# Flatcaster-sch.net
KiCad netlist of a schematic drawn in Altium Designer
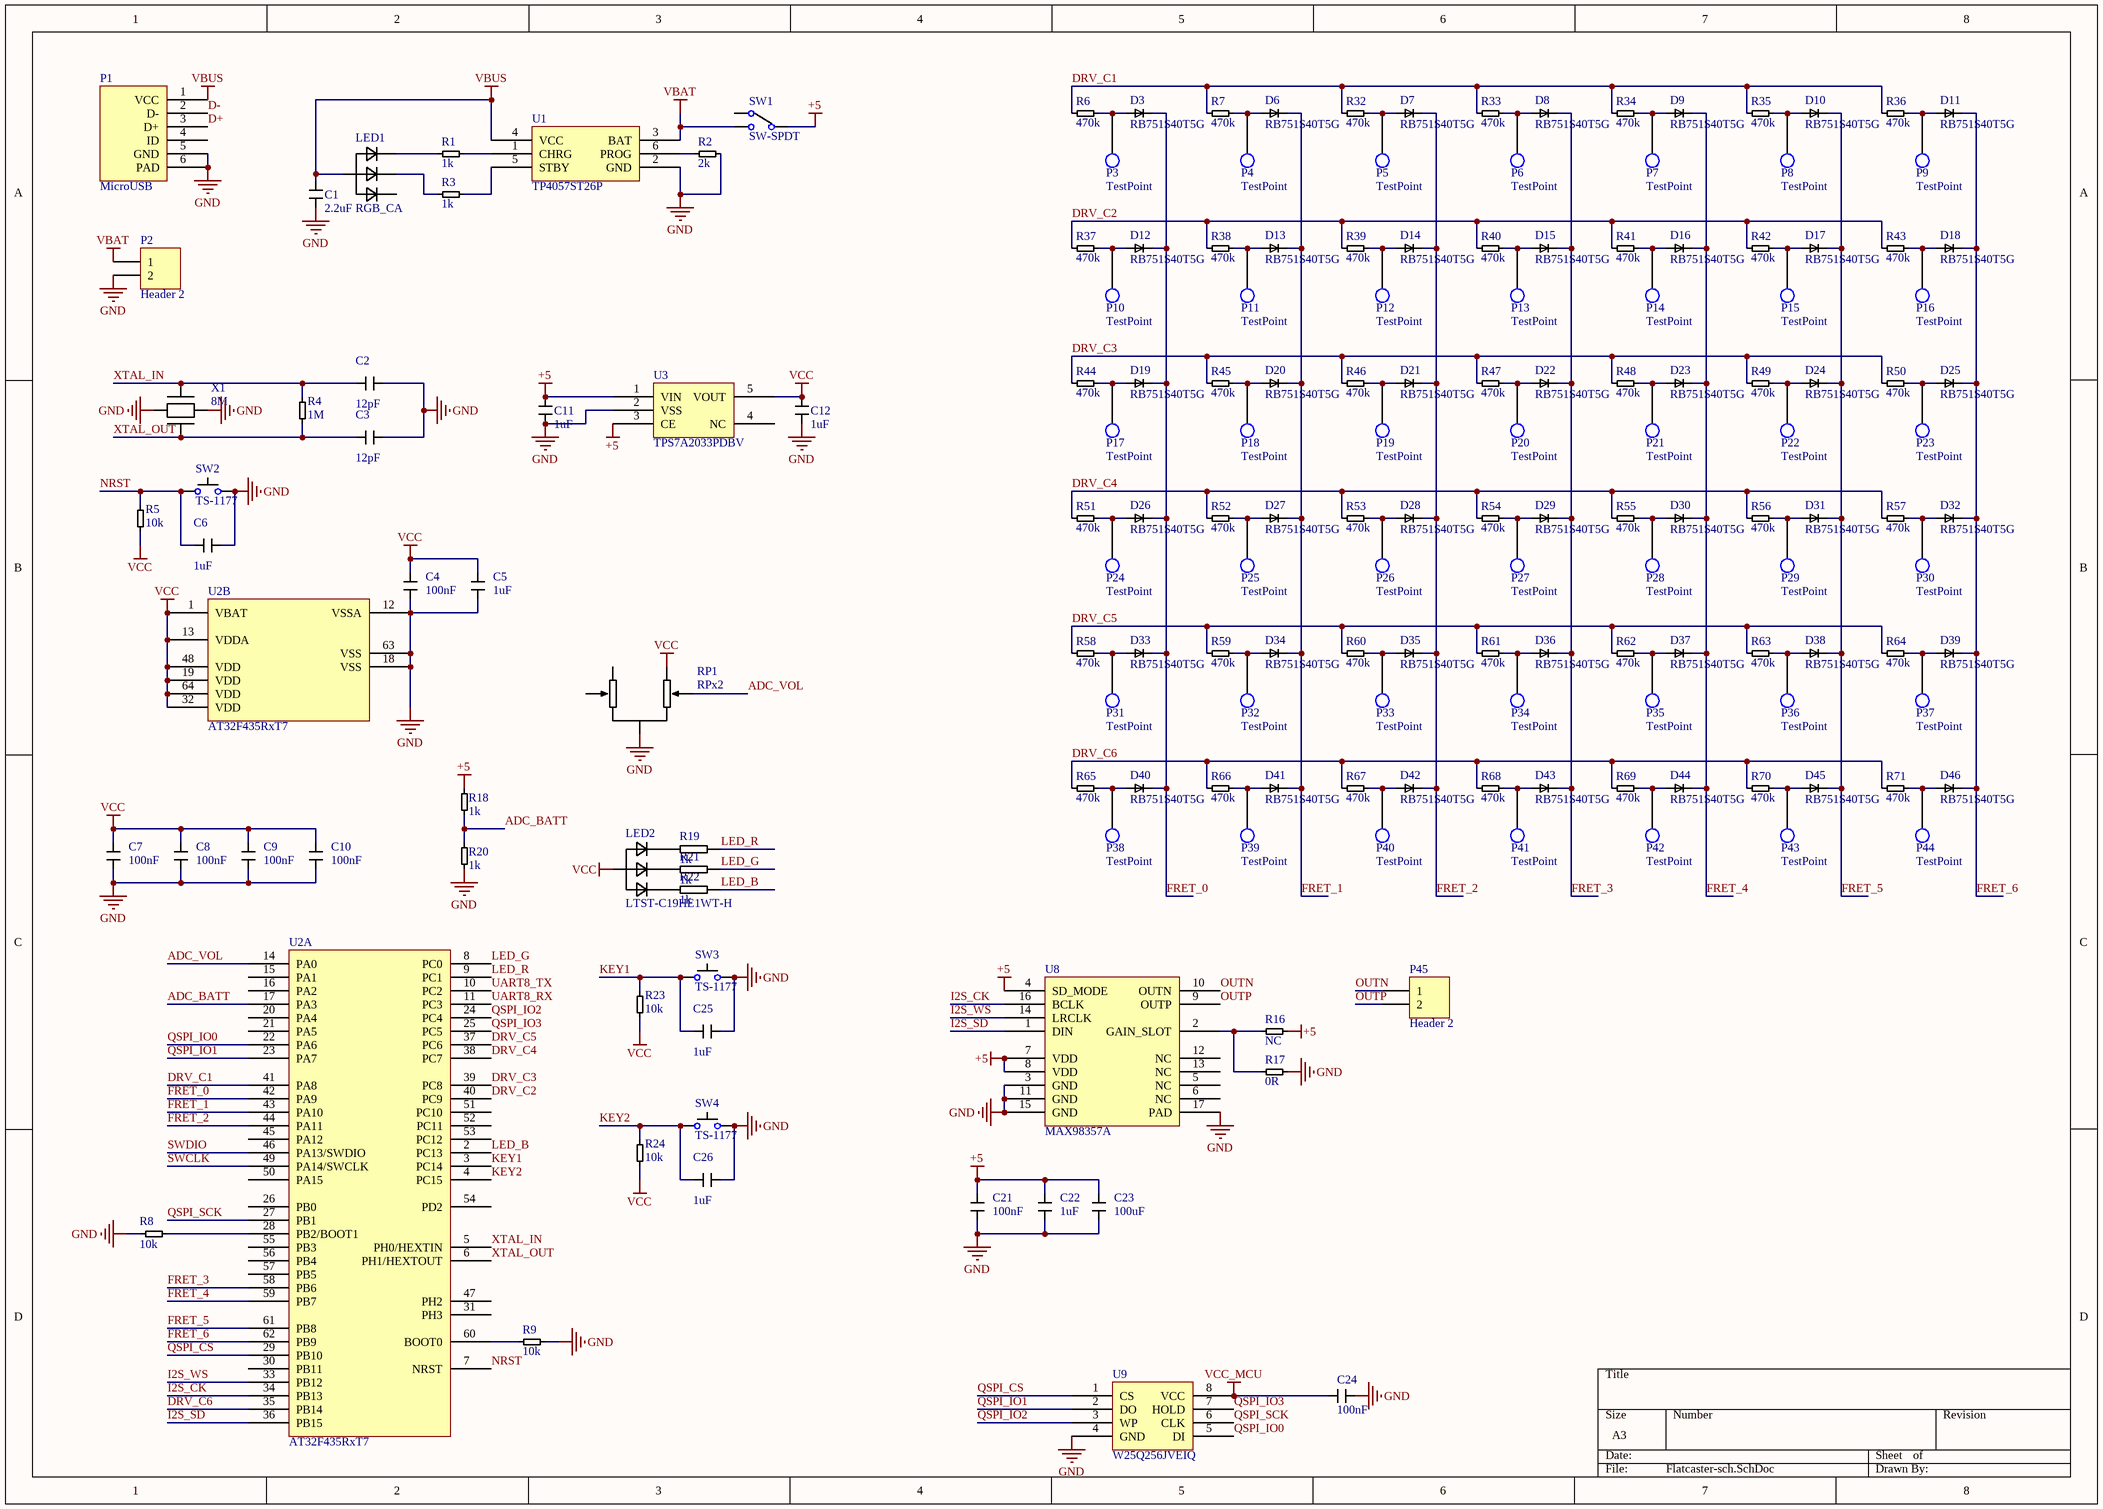
[diagram p0: Flatcaster-sch.SchDoc]

(export (version "E")
  (design (tool "Eeschema 10.0.6"))
  (components
    (comp (ref "C1") (value "2.2uF") (footprint "0603-Cap") (libsource (lib "LibCfrpg") (part "Cap")))
    (comp (ref "C2") (value "12pF") (footprint "0603-Cap") (libsource (lib "LibCfrpg") (part "Cap")))
    (comp (ref "C3") (value "12pF") (footprint "0603-Cap") (libsource (lib "LibCfrpg") (part "Cap")))
    (comp (ref "C4") (value "100nF") (footprint "0603-Cap") (libsource (lib "LibCfrpg") (part "Cap")))
    (comp (ref "C5") (value "1uF") (footprint "0603-Cap") (libsource (lib "LibCfrpg") (part "Cap")))
    (comp (ref "C6") (value "1uF") (footprint "0603-Cap") (libsource (lib "LibCfrpg") (part "Cap")))
    (comp (ref "C7") (value "100nF") (footprint "0603-Cap") (libsource (lib "LibCfrpg") (part "Cap")))
    (comp (ref "C8") (value "100nF") (footprint "0603-Cap") (libsource (lib "LibCfrpg") (part "Cap")))
    (comp (ref "C9") (value "100nF") (footprint "0603-Cap") (libsource (lib "LibCfrpg") (part "Cap")))
    (comp (ref "C10") (value "100nF") (footprint "0603-Cap") (libsource (lib "LibCfrpg") (part "Cap")))
    (comp (ref "C11") (value "1uF") (footprint "0603-Cap") (libsource (lib "LibCfrpg") (part "Cap")))
    (comp (ref "C12") (value "1uF") (footprint "0603-Cap") (libsource (lib "LibCfrpg") (part "Cap")))
    (comp (ref "C21") (value "100nF") (footprint "0603-Cap") (libsource (lib "LibCfrpg") (part "Cap")))
    (comp (ref "C22") (value "1uF") (footprint "0603-Cap") (libsource (lib "LibCfrpg") (part "Cap")))
    (comp (ref "C23") (value "100uF") (footprint "1206-C") (libsource (lib "LibCfrpg") (part "Cap")))
    (comp (ref "C24") (value "100nF") (footprint "0603-Cap") (libsource (lib "LibCfrpg") (part "Cap")))
    (comp (ref "C25") (value "1uF") (footprint "0603-Cap") (libsource (lib "LibCfrpg") (part "Cap")))
    (comp (ref "C26") (value "1uF") (footprint "0603-Cap") (libsource (lib "LibCfrpg") (part "Cap")))
    (comp (ref "D3") (value "RB751S40T5G") (footprint "SOD-523") (libsource (lib "LibCfrpg") (part "Diode")))
    (comp (ref "D6") (value "RB751S40T5G") (footprint "SOD-523") (libsource (lib "LibCfrpg") (part "Diode")))
    (comp (ref "D7") (value "RB751S40T5G") (footprint "SOD-523") (libsource (lib "LibCfrpg") (part "Diode")))
    (comp (ref "D8") (value "RB751S40T5G") (footprint "SOD-523") (libsource (lib "LibCfrpg") (part "Diode")))
    (comp (ref "D9") (value "RB751S40T5G") (footprint "SOD-523") (libsource (lib "LibCfrpg") (part "Diode")))
    (comp (ref "D10") (value "RB751S40T5G") (footprint "SOD-523") (libsource (lib "LibCfrpg") (part "Diode")))
    (comp (ref "D11") (value "RB751S40T5G") (footprint "SOD-523") (libsource (lib "LibCfrpg") (part "Diode")))
    (comp (ref "D12") (value "RB751S40T5G") (footprint "SOD-523") (libsource (lib "LibCfrpg") (part "Diode")))
    (comp (ref "D13") (value "RB751S40T5G") (footprint "SOD-523") (libsource (lib "LibCfrpg") (part "Diode")))
    (comp (ref "D14") (value "RB751S40T5G") (footprint "SOD-523") (libsource (lib "LibCfrpg") (part "Diode")))
    (comp (ref "D15") (value "RB751S40T5G") (footprint "SOD-523") (libsource (lib "LibCfrpg") (part "Diode")))
    (comp (ref "D16") (value "RB751S40T5G") (footprint "SOD-523") (libsource (lib "LibCfrpg") (part "Diode")))
    (comp (ref "D17") (value "RB751S40T5G") (footprint "SOD-523") (libsource (lib "LibCfrpg") (part "Diode")))
    (comp (ref "D18") (value "RB751S40T5G") (footprint "SOD-523") (libsource (lib "LibCfrpg") (part "Diode")))
    (comp (ref "D19") (value "RB751S40T5G") (footprint "SOD-523") (libsource (lib "LibCfrpg") (part "Diode")))
    (comp (ref "D20") (value "RB751S40T5G") (footprint "SOD-523") (libsource (lib "LibCfrpg") (part "Diode")))
    (comp (ref "D21") (value "RB751S40T5G") (footprint "SOD-523") (libsource (lib "LibCfrpg") (part "Diode")))
    (comp (ref "D22") (value "RB751S40T5G") (footprint "SOD-523") (libsource (lib "LibCfrpg") (part "Diode")))
    (comp (ref "D23") (value "RB751S40T5G") (footprint "SOD-523") (libsource (lib "LibCfrpg") (part "Diode")))
    (comp (ref "D24") (value "RB751S40T5G") (footprint "SOD-523") (libsource (lib "LibCfrpg") (part "Diode")))
    (comp (ref "D25") (value "RB751S40T5G") (footprint "SOD-523") (libsource (lib "LibCfrpg") (part "Diode")))
    (comp (ref "D26") (value "RB751S40T5G") (footprint "SOD-523") (libsource (lib "LibCfrpg") (part "Diode")))
    (comp (ref "D27") (value "RB751S40T5G") (footprint "SOD-523") (libsource (lib "LibCfrpg") (part "Diode")))
    (comp (ref "D28") (value "RB751S40T5G") (footprint "SOD-523") (libsource (lib "LibCfrpg") (part "Diode")))
    (comp (ref "D29") (value "RB751S40T5G") (footprint "SOD-523") (libsource (lib "LibCfrpg") (part "Diode")))
    (comp (ref "D30") (value "RB751S40T5G") (footprint "SOD-523") (libsource (lib "LibCfrpg") (part "Diode")))
    (comp (ref "D31") (value "RB751S40T5G") (footprint "SOD-523") (libsource (lib "LibCfrpg") (part "Diode")))
    (comp (ref "D32") (value "RB751S40T5G") (footprint "SOD-523") (libsource (lib "LibCfrpg") (part "Diode")))
    (comp (ref "D33") (value "RB751S40T5G") (footprint "SOD-523") (libsource (lib "LibCfrpg") (part "Diode")))
    (comp (ref "D34") (value "RB751S40T5G") (footprint "SOD-523") (libsource (lib "LibCfrpg") (part "Diode")))
    (comp (ref "D35") (value "RB751S40T5G") (footprint "SOD-523") (libsource (lib "LibCfrpg") (part "Diode")))
    (comp (ref "D36") (value "RB751S40T5G") (footprint "SOD-523") (libsource (lib "LibCfrpg") (part "Diode")))
    (comp (ref "D37") (value "RB751S40T5G") (footprint "SOD-523") (libsource (lib "LibCfrpg") (part "Diode")))
    (comp (ref "D38") (value "RB751S40T5G") (footprint "SOD-523") (libsource (lib "LibCfrpg") (part "Diode")))
    (comp (ref "D39") (value "RB751S40T5G") (footprint "SOD-523") (libsource (lib "LibCfrpg") (part "Diode")))
    (comp (ref "D40") (value "RB751S40T5G") (footprint "SOD-523") (libsource (lib "LibCfrpg") (part "Diode")))
    (comp (ref "D41") (value "RB751S40T5G") (footprint "SOD-523") (libsource (lib "LibCfrpg") (part "Diode")))
    (comp (ref "D42") (value "RB751S40T5G") (footprint "SOD-523") (libsource (lib "LibCfrpg") (part "Diode")))
    (comp (ref "D43") (value "RB751S40T5G") (footprint "SOD-523") (libsource (lib "LibCfrpg") (part "Diode")))
    (comp (ref "D44") (value "RB751S40T5G") (footprint "SOD-523") (libsource (lib "LibCfrpg") (part "Diode")))
    (comp (ref "D45") (value "RB751S40T5G") (footprint "SOD-523") (libsource (lib "LibCfrpg") (part "Diode")))
    (comp (ref "D46") (value "RB751S40T5G") (footprint "SOD-523") (libsource (lib "LibCfrpg") (part "Diode")))
    (comp (ref "LED1") (value "RGB_CA") (footprint "RGB1.6*1.6") (libsource (lib "LibCfrpg") (part "RGB_CA")))
    (comp (ref "LED2")
      (value "LTST-C19HE1WT-H")
      (footprint "RGB1.6*1.6")
      (description "C427425")
      (libsource (lib "LibCfrpg") (part "RGB_CA"))
    )
    (comp (ref "P1") (value "MicroUSB") (footprint "MicroUSB") (libsource (lib "LibCfrpg") (part "MicroUSB")))
    (comp (ref "P2")
      (value "Header 2")
      (footprint "LibCfrpg:SH2.0 2P")
      (description "Header, 2-Pin")
      (fields (field (name "PUBLISHER") "Altium Limited"))
      (libsource (lib "Miscellaneous Connectors") (part "Header 2"))
    )
    (comp (ref "P3")
      (value "TestPoint")
      (footprint "TestPoint")
      (libsource (lib "LibCfrpg") (part "TestPoint"))
    )
    (comp (ref "P4")
      (value "TestPoint")
      (footprint "TestPoint")
      (libsource (lib "LibCfrpg") (part "TestPoint"))
    )
    (comp (ref "P5")
      (value "TestPoint")
      (footprint "TestPoint")
      (libsource (lib "LibCfrpg") (part "TestPoint"))
    )
    (comp (ref "P6")
      (value "TestPoint")
      (footprint "TestPoint")
      (libsource (lib "LibCfrpg") (part "TestPoint"))
    )
    (comp (ref "P7")
      (value "TestPoint")
      (footprint "TestPoint")
      (libsource (lib "LibCfrpg") (part "TestPoint"))
    )
    (comp (ref "P8")
      (value "TestPoint")
      (footprint "TestPoint")
      (libsource (lib "LibCfrpg") (part "TestPoint"))
    )
    (comp (ref "P9")
      (value "TestPoint")
      (footprint "TestPoint")
      (libsource (lib "LibCfrpg") (part "TestPoint"))
    )
    (comp (ref "P10")
      (value "TestPoint")
      (footprint "TestPoint")
      (libsource (lib "LibCfrpg") (part "TestPoint"))
    )
    (comp (ref "P11")
      (value "TestPoint")
      (footprint "TestPoint")
      (libsource (lib "LibCfrpg") (part "TestPoint"))
    )
    (comp (ref "P12")
      (value "TestPoint")
      (footprint "TestPoint")
      (libsource (lib "LibCfrpg") (part "TestPoint"))
    )
    (comp (ref "P13")
      (value "TestPoint")
      (footprint "TestPoint")
      (libsource (lib "LibCfrpg") (part "TestPoint"))
    )
    (comp (ref "P14")
      (value "TestPoint")
      (footprint "TestPoint")
      (libsource (lib "LibCfrpg") (part "TestPoint"))
    )
    (comp (ref "P15")
      (value "TestPoint")
      (footprint "TestPoint")
      (libsource (lib "LibCfrpg") (part "TestPoint"))
    )
    (comp (ref "P16")
      (value "TestPoint")
      (footprint "TestPoint")
      (libsource (lib "LibCfrpg") (part "TestPoint"))
    )
    (comp (ref "P17")
      (value "TestPoint")
      (footprint "TestPoint")
      (libsource (lib "LibCfrpg") (part "TestPoint"))
    )
    (comp (ref "P18")
      (value "TestPoint")
      (footprint "TestPoint")
      (libsource (lib "LibCfrpg") (part "TestPoint"))
    )
    (comp (ref "P19")
      (value "TestPoint")
      (footprint "TestPoint")
      (libsource (lib "LibCfrpg") (part "TestPoint"))
    )
    (comp (ref "P20")
      (value "TestPoint")
      (footprint "TestPoint")
      (libsource (lib "LibCfrpg") (part "TestPoint"))
    )
    (comp (ref "P21")
      (value "TestPoint")
      (footprint "TestPoint")
      (libsource (lib "LibCfrpg") (part "TestPoint"))
    )
    (comp (ref "P22")
      (value "TestPoint")
      (footprint "TestPoint")
      (libsource (lib "LibCfrpg") (part "TestPoint"))
    )
    (comp (ref "P23")
      (value "TestPoint")
      (footprint "TestPoint")
      (libsource (lib "LibCfrpg") (part "TestPoint"))
    )
    (comp (ref "P24")
      (value "TestPoint")
      (footprint "TestPoint")
      (libsource (lib "LibCfrpg") (part "TestPoint"))
    )
    (comp (ref "P25")
      (value "TestPoint")
      (footprint "TestPoint")
      (libsource (lib "LibCfrpg") (part "TestPoint"))
    )
    (comp (ref "P26")
      (value "TestPoint")
      (footprint "TestPoint")
      (libsource (lib "LibCfrpg") (part "TestPoint"))
    )
    (comp (ref "P27")
      (value "TestPoint")
      (footprint "TestPoint")
      (libsource (lib "LibCfrpg") (part "TestPoint"))
    )
    (comp (ref "P28")
      (value "TestPoint")
      (footprint "TestPoint")
      (libsource (lib "LibCfrpg") (part "TestPoint"))
    )
    (comp (ref "P29")
      (value "TestPoint")
      (footprint "TestPoint")
      (libsource (lib "LibCfrpg") (part "TestPoint"))
    )
    (comp (ref "P30")
      (value "TestPoint")
      (footprint "TestPoint")
      (libsource (lib "LibCfrpg") (part "TestPoint"))
    )
    (comp (ref "P31")
      (value "TestPoint")
      (footprint "TestPoint")
      (libsource (lib "LibCfrpg") (part "TestPoint"))
    )
    (comp (ref "P32")
      (value "TestPoint")
      (footprint "TestPoint")
      (libsource (lib "LibCfrpg") (part "TestPoint"))
    )
    (comp (ref "P33")
      (value "TestPoint")
      (footprint "TestPoint")
      (libsource (lib "LibCfrpg") (part "TestPoint"))
    )
    (comp (ref "P34")
      (value "TestPoint")
      (footprint "TestPoint")
      (libsource (lib "LibCfrpg") (part "TestPoint"))
    )
    (comp (ref "P35")
      (value "TestPoint")
      (footprint "TestPoint")
      (libsource (lib "LibCfrpg") (part "TestPoint"))
    )
    (comp (ref "P36")
      (value "TestPoint")
      (footprint "TestPoint")
      (libsource (lib "LibCfrpg") (part "TestPoint"))
    )
    (comp (ref "P37")
      (value "TestPoint")
      (footprint "TestPoint")
      (libsource (lib "LibCfrpg") (part "TestPoint"))
    )
    (comp (ref "P38")
      (value "TestPoint")
      (footprint "TestPoint")
      (libsource (lib "LibCfrpg") (part "TestPoint"))
    )
    (comp (ref "P39")
      (value "TestPoint")
      (footprint "TestPoint")
      (libsource (lib "LibCfrpg") (part "TestPoint"))
    )
    (comp (ref "P40")
      (value "TestPoint")
      (footprint "TestPoint")
      (libsource (lib "LibCfrpg") (part "TestPoint"))
    )
    (comp (ref "P41")
      (value "TestPoint")
      (footprint "TestPoint")
      (libsource (lib "LibCfrpg") (part "TestPoint"))
    )
    (comp (ref "P42")
      (value "TestPoint")
      (footprint "TestPoint")
      (libsource (lib "LibCfrpg") (part "TestPoint"))
    )
    (comp (ref "P43")
      (value "TestPoint")
      (footprint "TestPoint")
      (libsource (lib "LibCfrpg") (part "TestPoint"))
    )
    (comp (ref "P44")
      (value "TestPoint")
      (footprint "TestPoint")
      (libsource (lib "LibCfrpg") (part "TestPoint"))
    )
    (comp (ref "P45")
      (value "Header 2")
      (footprint "HDR1X2")
      (description "Header, 2-Pin")
      (fields (field (name "PUBLISHER") "Altium Limited"))
      (libsource (lib "Miscellaneous Connectors") (part "Header 2"))
    )
    (comp (ref "R1") (value "1k") (footprint "0603") (libsource (lib "LibCfrpg") (part "Res")))
    (comp (ref "R2") (value "2k") (footprint "0603") (libsource (lib "LibCfrpg") (part "Res")))
    (comp (ref "R3") (value "1k") (footprint "0603") (libsource (lib "LibCfrpg") (part "Res")))
    (comp (ref "R4") (value "1M") (footprint "0603") (libsource (lib "LibCfrpg") (part "Res")))
    (comp (ref "R5") (value "10k") (footprint "0603") (libsource (lib "LibCfrpg") (part "Res")))
    (comp (ref "R6") (value "470k") (footprint "0603") (libsource (lib "LibCfrpg") (part "Res")))
    (comp (ref "R7") (value "470k") (footprint "0603") (libsource (lib "LibCfrpg") (part "Res")))
    (comp (ref "R8") (value "10k") (footprint "0603") (libsource (lib "LibCfrpg") (part "Res")))
    (comp (ref "R9") (value "10k") (footprint "0603") (libsource (lib "LibCfrpg") (part "Res")))
    (comp (ref "R16") (value "NC") (footprint "0603") (libsource (lib "LibCfrpg") (part "Res")))
    (comp (ref "R17") (value "0R") (footprint "0603") (libsource (lib "LibCfrpg") (part "Res")))
    (comp (ref "R18") (value "1k") (footprint "0603") (libsource (lib "LibCfrpg") (part "Res")))
    (comp (ref "R19") (value "1k") (footprint "0603") (libsource (lib "") (part "Res_1")))
    (comp (ref "R20") (value "1k") (footprint "0603") (libsource (lib "LibCfrpg") (part "Res")))
    (comp (ref "R21") (value "1k") (footprint "0603") (libsource (lib "") (part "Res_1")))
    (comp (ref "R22") (value "1k") (footprint "0603") (libsource (lib "") (part "Res_1")))
    (comp (ref "R23") (value "10k") (footprint "0603") (libsource (lib "LibCfrpg") (part "Res")))
    (comp (ref "R24") (value "10k") (footprint "0603") (libsource (lib "LibCfrpg") (part "Res")))
    (comp (ref "R32") (value "470k") (footprint "0603") (libsource (lib "LibCfrpg") (part "Res")))
    (comp (ref "R33") (value "470k") (footprint "0603") (libsource (lib "LibCfrpg") (part "Res")))
    (comp (ref "R34") (value "470k") (footprint "0603") (libsource (lib "LibCfrpg") (part "Res")))
    (comp (ref "R35") (value "470k") (footprint "0603") (libsource (lib "LibCfrpg") (part "Res")))
    (comp (ref "R36") (value "470k") (footprint "0603") (libsource (lib "LibCfrpg") (part "Res")))
    (comp (ref "R37") (value "470k") (footprint "0603") (libsource (lib "LibCfrpg") (part "Res")))
    (comp (ref "R38") (value "470k") (footprint "0603") (libsource (lib "LibCfrpg") (part "Res")))
    (comp (ref "R39") (value "470k") (footprint "0603") (libsource (lib "LibCfrpg") (part "Res")))
    (comp (ref "R40") (value "470k") (footprint "0603") (libsource (lib "LibCfrpg") (part "Res")))
    (comp (ref "R41") (value "470k") (footprint "0603") (libsource (lib "LibCfrpg") (part "Res")))
    (comp (ref "R42") (value "470k") (footprint "0603") (libsource (lib "LibCfrpg") (part "Res")))
    (comp (ref "R43") (value "470k") (footprint "0603") (libsource (lib "LibCfrpg") (part "Res")))
    (comp (ref "R44") (value "470k") (footprint "0603") (libsource (lib "LibCfrpg") (part "Res")))
    (comp (ref "R45") (value "470k") (footprint "0603") (libsource (lib "LibCfrpg") (part "Res")))
    (comp (ref "R46") (value "470k") (footprint "0603") (libsource (lib "LibCfrpg") (part "Res")))
    (comp (ref "R47") (value "470k") (footprint "0603") (libsource (lib "LibCfrpg") (part "Res")))
    (comp (ref "R48") (value "470k") (footprint "0603") (libsource (lib "LibCfrpg") (part "Res")))
    (comp (ref "R49") (value "470k") (footprint "0603") (libsource (lib "LibCfrpg") (part "Res")))
    (comp (ref "R50") (value "470k") (footprint "0603") (libsource (lib "LibCfrpg") (part "Res")))
    (comp (ref "R51") (value "470k") (footprint "0603") (libsource (lib "LibCfrpg") (part "Res")))
    (comp (ref "R52") (value "470k") (footprint "0603") (libsource (lib "LibCfrpg") (part "Res")))
    (comp (ref "R53") (value "470k") (footprint "0603") (libsource (lib "LibCfrpg") (part "Res")))
    (comp (ref "R54") (value "470k") (footprint "0603") (libsource (lib "LibCfrpg") (part "Res")))
    (comp (ref "R55") (value "470k") (footprint "0603") (libsource (lib "LibCfrpg") (part "Res")))
    (comp (ref "R56") (value "470k") (footprint "0603") (libsource (lib "LibCfrpg") (part "Res")))
    (comp (ref "R57") (value "470k") (footprint "0603") (libsource (lib "LibCfrpg") (part "Res")))
    (comp (ref "R58") (value "470k") (footprint "0603") (libsource (lib "LibCfrpg") (part "Res")))
    (comp (ref "R59") (value "470k") (footprint "0603") (libsource (lib "LibCfrpg") (part "Res")))
    (comp (ref "R60") (value "470k") (footprint "0603") (libsource (lib "LibCfrpg") (part "Res")))
    (comp (ref "R61") (value "470k") (footprint "0603") (libsource (lib "LibCfrpg") (part "Res")))
    (comp (ref "R62") (value "470k") (footprint "0603") (libsource (lib "LibCfrpg") (part "Res")))
    (comp (ref "R63") (value "470k") (footprint "0603") (libsource (lib "LibCfrpg") (part "Res")))
    (comp (ref "R64") (value "470k") (footprint "0603") (libsource (lib "LibCfrpg") (part "Res")))
    (comp (ref "R65") (value "470k") (footprint "0603") (libsource (lib "LibCfrpg") (part "Res")))
    (comp (ref "R66") (value "470k") (footprint "0603") (libsource (lib "LibCfrpg") (part "Res")))
    (comp (ref "R67") (value "470k") (footprint "0603") (libsource (lib "LibCfrpg") (part "Res")))
    (comp (ref "R68") (value "470k") (footprint "0603") (libsource (lib "LibCfrpg") (part "Res")))
    (comp (ref "R69") (value "470k") (footprint "0603") (libsource (lib "LibCfrpg") (part "Res")))
    (comp (ref "R70") (value "470k") (footprint "0603") (libsource (lib "LibCfrpg") (part "Res")))
    (comp (ref "R71") (value "470k") (footprint "0603") (libsource (lib "LibCfrpg") (part "Res")))
    (comp (ref "RP1") (value "RPx2") (footprint "RK10J") (libsource (lib "LibCfrpg") (part "RPx2")))
    (comp (ref "SW1")
      (value "SW-SPDT")
      (footprint "TA-3524A-A1")
      (description "C514014")
      (libsource (lib "LibCfrpg") (part "SW-SPDT"))
    )
    (comp (ref "SW2")
      (value "TS-1177")
      (footprint "BTN3*3")
      (description "C561512")
      (libsource (lib "LibCfrpg") (part "Btn"))
    )
    (comp (ref "SW3")
      (value "TS-1177")
      (footprint "BTN3*3")
      (description "C561512")
      (libsource (lib "LibCfrpg") (part "Btn"))
    )
    (comp (ref "SW4")
      (value "TS-1177")
      (footprint "BTN3*3")
      (description "C561512")
      (libsource (lib "LibCfrpg") (part "Btn"))
    )
    (comp (ref "U1")
      (value "TP4057ST26P")
      (footprint "SOT236")
      (libsource (lib "LibCfrpg") (part "TP4057ST26P"))
    )
    (comp (ref "U2")
      (value "AT32F435RxT7")
      (footprint "LQFP-64")
      (libsource (lib "LibCfrpg") (part "AT32F435RxT7"))
    )
    (comp (ref "U3")
      (value "TPS7A2033PDBV")
      (footprint "SOT23-5")
      (libsource (lib "LibCfrpg") (part "ME6211"))
    )
    (comp (ref "U8")
      (value "MAX98357A")
      (footprint "QFN16-0.5-1.1PAD")
      (libsource (lib "LibCfrpg") (part "MAX98357A"))
    )
    (comp (ref "U9")
      (value "W25Q256JVEIQ")
      (footprint "WPDFN-8-6x5")
      (libsource (lib "LibCfrpg") (part "W25QxxxVE/A"))
    )
    (comp (ref "X1")
      (value "8M")
      (footprint "XTAL-3225-4P")
      (description "C2682774")
      (libsource (lib "LibCfrpg") (part "XTAL-4LEAD"))
    )
  )
  (nets
    (net (code "1") (name "+5") (class "Default")
      (node (ref "C11") (pin "2") (pintype "passive"))
      (node (ref "C21") (pin "2") (pintype "passive"))
      (node (ref "C22") (pin "2") (pintype "passive"))
      (node (ref "C23") (pin "2") (pintype "passive"))
      (node (ref "R16") (pin "1") (pintype "passive"))
      (node (ref "R18") (pin "2") (pintype "passive"))
      (node (ref "SW1") (pin "1") (pintype "passive"))
      (node (ref "U3") (pin "1") (pinfunction "VIN_1") (pintype "passive"))
      (node (ref "U3") (pin "3") (pinfunction "CE_3") (pintype "passive"))
      (node (ref "U8") (pin "4") (pinfunction "SD_MODE_4") (pintype "passive"))
      (node (ref "U8") (pin "7") (pinfunction "VDD_7") (pintype "passive"))
      (node (ref "U8") (pin "8") (pinfunction "VDD_8") (pintype "passive"))
    )
    (net (code "2") (name "/ADC_BATT") (class "Default")
      (node (ref "R18") (pin "1") (pintype "passive"))
      (node (ref "R20") (pin "2") (pintype "passive"))
      (node (ref "U2") (pin "17") (pinfunction "PA3_17") (pintype "passive"))
    )
    (net (code "3") (name "/ADC_VOL") (class "Default")
      (node (ref "RP1") (pin "3") (pintype "passive"))
      (node (ref "U2") (pin "14") (pinfunction "PA0_14") (pintype "passive"))
    )
    (net (code "4") (name "/D+") (class "Default")
      (node (ref "P1") (pin "3") (pinfunction "D+_3") (pintype "passive"))
    )
    (net (code "5") (name "/D-") (class "Default")
      (node (ref "P1") (pin "2") (pinfunction "D-_2") (pintype "passive"))
    )
    (net (code "6") (name "/DRV_C1") (class "Default")
      (node (ref "R32") (pin "1") (pintype "passive"))
      (node (ref "R33") (pin "1") (pintype "passive"))
      (node (ref "R34") (pin "1") (pintype "passive"))
      (node (ref "R35") (pin "1") (pintype "passive"))
      (node (ref "R36") (pin "1") (pintype "passive"))
      (node (ref "R6") (pin "1") (pintype "passive"))
      (node (ref "R7") (pin "1") (pintype "passive"))
      (node (ref "U2") (pin "41") (pinfunction "PA8_41") (pintype "passive"))
    )
    (net (code "7") (name "/DRV_C2") (class "Default")
      (node (ref "R37") (pin "1") (pintype "passive"))
      (node (ref "R38") (pin "1") (pintype "passive"))
      (node (ref "R39") (pin "1") (pintype "passive"))
      (node (ref "R40") (pin "1") (pintype "passive"))
      (node (ref "R41") (pin "1") (pintype "passive"))
      (node (ref "R42") (pin "1") (pintype "passive"))
      (node (ref "R43") (pin "1") (pintype "passive"))
      (node (ref "U2") (pin "40") (pinfunction "PC9_40") (pintype "passive"))
    )
    (net (code "8") (name "/DRV_C3") (class "Default")
      (node (ref "R44") (pin "1") (pintype "passive"))
      (node (ref "R45") (pin "1") (pintype "passive"))
      (node (ref "R46") (pin "1") (pintype "passive"))
      (node (ref "R47") (pin "1") (pintype "passive"))
      (node (ref "R48") (pin "1") (pintype "passive"))
      (node (ref "R49") (pin "1") (pintype "passive"))
      (node (ref "R50") (pin "1") (pintype "passive"))
      (node (ref "U2") (pin "39") (pinfunction "PC8_39") (pintype "passive"))
    )
    (net (code "9") (name "/DRV_C4") (class "Default")
      (node (ref "R51") (pin "1") (pintype "passive"))
      (node (ref "R52") (pin "1") (pintype "passive"))
      (node (ref "R53") (pin "1") (pintype "passive"))
      (node (ref "R54") (pin "1") (pintype "passive"))
      (node (ref "R55") (pin "1") (pintype "passive"))
      (node (ref "R56") (pin "1") (pintype "passive"))
      (node (ref "R57") (pin "1") (pintype "passive"))
      (node (ref "U2") (pin "38") (pinfunction "PC7_38") (pintype "passive"))
    )
    (net (code "10") (name "/DRV_C5") (class "Default")
      (node (ref "R58") (pin "1") (pintype "passive"))
      (node (ref "R59") (pin "1") (pintype "passive"))
      (node (ref "R60") (pin "1") (pintype "passive"))
      (node (ref "R61") (pin "1") (pintype "passive"))
      (node (ref "R62") (pin "1") (pintype "passive"))
      (node (ref "R63") (pin "1") (pintype "passive"))
      (node (ref "R64") (pin "1") (pintype "passive"))
      (node (ref "U2") (pin "37") (pinfunction "PC6_37") (pintype "passive"))
    )
    (net (code "11") (name "/DRV_C6") (class "Default")
      (node (ref "R65") (pin "1") (pintype "passive"))
      (node (ref "R66") (pin "1") (pintype "passive"))
      (node (ref "R67") (pin "1") (pintype "passive"))
      (node (ref "R68") (pin "1") (pintype "passive"))
      (node (ref "R69") (pin "1") (pintype "passive"))
      (node (ref "R70") (pin "1") (pintype "passive"))
      (node (ref "R71") (pin "1") (pintype "passive"))
      (node (ref "U2") (pin "35") (pinfunction "PB14_35") (pintype "passive"))
    )
    (net (code "12") (name "/FRET_0") (class "Default")
      (node (ref "D12") (pin "2") (pintype "passive"))
      (node (ref "D19") (pin "2") (pintype "passive"))
      (node (ref "D26") (pin "2") (pintype "passive"))
      (node (ref "D3") (pin "2") (pintype "passive"))
      (node (ref "D33") (pin "2") (pintype "passive"))
      (node (ref "D40") (pin "2") (pintype "passive"))
      (node (ref "U2") (pin "42") (pinfunction "PA9_42") (pintype "passive"))
    )
    (net (code "13") (name "/FRET_1") (class "Default")
      (node (ref "D13") (pin "2") (pintype "passive"))
      (node (ref "D20") (pin "2") (pintype "passive"))
      (node (ref "D27") (pin "2") (pintype "passive"))
      (node (ref "D34") (pin "2") (pintype "passive"))
      (node (ref "D41") (pin "2") (pintype "passive"))
      (node (ref "D6") (pin "2") (pintype "passive"))
      (node (ref "U2") (pin "43") (pinfunction "PA10_43") (pintype "passive"))
    )
    (net (code "14") (name "/FRET_2") (class "Default")
      (node (ref "D14") (pin "2") (pintype "passive"))
      (node (ref "D21") (pin "2") (pintype "passive"))
      (node (ref "D28") (pin "2") (pintype "passive"))
      (node (ref "D35") (pin "2") (pintype "passive"))
      (node (ref "D42") (pin "2") (pintype "passive"))
      (node (ref "D7") (pin "2") (pintype "passive"))
      (node (ref "U2") (pin "44") (pinfunction "PA11_44") (pintype "passive"))
    )
    (net (code "15") (name "/FRET_3") (class "Default")
      (node (ref "D15") (pin "2") (pintype "passive"))
      (node (ref "D22") (pin "2") (pintype "passive"))
      (node (ref "D29") (pin "2") (pintype "passive"))
      (node (ref "D36") (pin "2") (pintype "passive"))
      (node (ref "D43") (pin "2") (pintype "passive"))
      (node (ref "D8") (pin "2") (pintype "passive"))
      (node (ref "U2") (pin "58") (pinfunction "PB6_58") (pintype "passive"))
    )
    (net (code "16") (name "/FRET_4") (class "Default")
      (node (ref "D16") (pin "2") (pintype "passive"))
      (node (ref "D23") (pin "2") (pintype "passive"))
      (node (ref "D30") (pin "2") (pintype "passive"))
      (node (ref "D37") (pin "2") (pintype "passive"))
      (node (ref "D44") (pin "2") (pintype "passive"))
      (node (ref "D9") (pin "2") (pintype "passive"))
      (node (ref "U2") (pin "59") (pinfunction "PB7_59") (pintype "passive"))
    )
    (net (code "17") (name "/FRET_5") (class "Default")
      (node (ref "D10") (pin "2") (pintype "passive"))
      (node (ref "D17") (pin "2") (pintype "passive"))
      (node (ref "D24") (pin "2") (pintype "passive"))
      (node (ref "D31") (pin "2") (pintype "passive"))
      (node (ref "D38") (pin "2") (pintype "passive"))
      (node (ref "D45") (pin "2") (pintype "passive"))
      (node (ref "U2") (pin "61") (pinfunction "PB8_61") (pintype "passive"))
    )
    (net (code "18") (name "/FRET_6") (class "Default")
      (node (ref "D11") (pin "2") (pintype "passive"))
      (node (ref "D18") (pin "2") (pintype "passive"))
      (node (ref "D25") (pin "2") (pintype "passive"))
      (node (ref "D32") (pin "2") (pintype "passive"))
      (node (ref "D39") (pin "2") (pintype "passive"))
      (node (ref "D46") (pin "2") (pintype "passive"))
      (node (ref "U2") (pin "62") (pinfunction "PB9_62") (pintype "passive"))
    )
    (net (code "19") (name "/I2S_CK") (class "Default")
      (node (ref "U2") (pin "34") (pinfunction "PB13_34") (pintype "passive"))
      (node (ref "U8") (pin "16") (pinfunction "BCLK_16") (pintype "passive"))
    )
    (net (code "20") (name "/I2S_SD") (class "Default")
      (node (ref "U2") (pin "36") (pinfunction "PB15_36") (pintype "passive"))
      (node (ref "U8") (pin "1") (pinfunction "DIN_1") (pintype "passive"))
    )
    (net (code "21") (name "/I2S_WS") (class "Default")
      (node (ref "U2") (pin "33") (pinfunction "PB12_33") (pintype "passive"))
      (node (ref "U8") (pin "14") (pinfunction "LRCLK_14") (pintype "passive"))
    )
    (net (code "22") (name "/KEY1") (class "Default")
      (node (ref "C25") (pin "2") (pintype "passive"))
      (node (ref "R23") (pin "2") (pintype "passive"))
      (node (ref "SW3") (pin "1") (pintype "passive"))
      (node (ref "U2") (pin "3") (pinfunction "PC14_3") (pintype "passive"))
    )
    (net (code "23") (name "/KEY2") (class "Default")
      (node (ref "C26") (pin "2") (pintype "passive"))
      (node (ref "R24") (pin "2") (pintype "passive"))
      (node (ref "SW4") (pin "1") (pintype "passive"))
      (node (ref "U2") (pin "4") (pinfunction "PC15_4") (pintype "passive"))
    )
    (net (code "24") (name "/LED_B") (class "Default")
      (node (ref "R22") (pin "2") (pintype "passive"))
      (node (ref "U2") (pin "2") (pinfunction "PC13_2") (pintype "passive"))
    )
    (net (code "25") (name "/LED_G") (class "Default")
      (node (ref "R21") (pin "2") (pintype "passive"))
      (node (ref "U2") (pin "8") (pinfunction "PC0_8") (pintype "passive"))
    )
    (net (code "26") (name "/LED_R") (class "Default")
      (node (ref "R19") (pin "2") (pintype "passive"))
      (node (ref "U2") (pin "9") (pinfunction "PC1_9") (pintype "passive"))
    )
    (net (code "27") (name "/NRST") (class "Default")
      (node (ref "C6") (pin "2") (pintype "passive"))
      (node (ref "R5") (pin "2") (pintype "passive"))
      (node (ref "SW2") (pin "1") (pintype "passive"))
      (node (ref "U2") (pin "7") (pinfunction "NRST_7") (pintype "passive"))
    )
    (net (code "28") (name "/OUTN") (class "Default")
      (node (ref "P45") (pin "1") (pinfunction "1_1") (pintype "passive"))
      (node (ref "U8") (pin "10") (pinfunction "OUTN_10") (pintype "passive"))
    )
    (net (code "29") (name "/OUTP") (class "Default")
      (node (ref "P45") (pin "2") (pinfunction "2_2") (pintype "passive"))
      (node (ref "U8") (pin "9") (pinfunction "OUTP_9") (pintype "passive"))
    )
    (net (code "30") (name "/QSPI_CS") (class "Default")
      (node (ref "U2") (pin "29") (pinfunction "PB10_29") (pintype "passive"))
      (node (ref "U9") (pin "1") (pinfunction "CS_1") (pintype "passive"))
    )
    (net (code "31") (name "/QSPI_IO0") (class "Default")
      (node (ref "U2") (pin "22") (pinfunction "PA6_22") (pintype "passive"))
      (node (ref "U9") (pin "5") (pinfunction "DI_5") (pintype "passive"))
    )
    (net (code "32") (name "/QSPI_IO1") (class "Default")
      (node (ref "U2") (pin "23") (pinfunction "PA7_23") (pintype "passive"))
      (node (ref "U9") (pin "2") (pinfunction "DO_2") (pintype "passive"))
    )
    (net (code "33") (name "/QSPI_IO2") (class "Default")
      (node (ref "U2") (pin "24") (pinfunction "PC4_24") (pintype "passive"))
      (node (ref "U9") (pin "3") (pinfunction "WP_3") (pintype "passive"))
    )
    (net (code "34") (name "/QSPI_IO3") (class "Default")
      (node (ref "U2") (pin "25") (pinfunction "PC5_25") (pintype "passive"))
      (node (ref "U9") (pin "7") (pinfunction "HOLD_7") (pintype "passive"))
    )
    (net (code "35") (name "/QSPI_SCK") (class "Default")
      (node (ref "U2") (pin "27") (pinfunction "PB1_27") (pintype "passive"))
      (node (ref "U9") (pin "6") (pinfunction "CLK_6") (pintype "passive"))
    )
    (net (code "36") (name "/SWCLK") (class "Default")
      (node (ref "U2") (pin "49") (pinfunction "PA14/SWCLK_49") (pintype "passive"))
    )
    (net (code "37") (name "/SWDIO") (class "Default")
      (node (ref "U2") (pin "46") (pinfunction "PA13/SWDIO_46") (pintype "passive"))
    )
    (net (code "38") (name "/UART8_RX") (class "Default")
      (node (ref "U2") (pin "11") (pinfunction "PC3_11") (pintype "passive"))
    )
    (net (code "39") (name "/UART8_TX") (class "Default")
      (node (ref "U2") (pin "10") (pinfunction "PC2_10") (pintype "passive"))
    )
    (net (code "40") (name "/XTAL_IN") (class "Default")
      (node (ref "C2") (pin "2") (pintype "passive"))
      (node (ref "R4") (pin "2") (pintype "passive"))
      (node (ref "U2") (pin "5") (pinfunction "PH0/HEXTIN_5") (pintype "passive"))
      (node (ref "X1") (pin "3") (pintype "passive"))
    )
    (net (code "41") (name "/XTAL_OUT") (class "Default")
      (node (ref "C3") (pin "2") (pintype "passive"))
      (node (ref "R4") (pin "1") (pintype "passive"))
      (node (ref "U2") (pin "6") (pinfunction "PH1/HEXTOUT_6") (pintype "passive"))
      (node (ref "X1") (pin "1") (pintype "passive"))
    )
    (net (code "42") (name "GND") (class "Default")
      (node (ref "C1") (pin "1") (pintype "passive"))
      (node (ref "C10") (pin "1") (pintype "passive"))
      (node (ref "C11") (pin "1") (pintype "passive"))
      (node (ref "C12") (pin "1") (pintype "passive"))
      (node (ref "C2") (pin "1") (pintype "passive"))
      (node (ref "C21") (pin "1") (pintype "passive"))
      (node (ref "C22") (pin "1") (pintype "passive"))
      (node (ref "C23") (pin "1") (pintype "passive"))
      (node (ref "C24") (pin "1") (pintype "passive"))
      (node (ref "C25") (pin "1") (pintype "passive"))
      (node (ref "C26") (pin "1") (pintype "passive"))
      (node (ref "C3") (pin "1") (pintype "passive"))
      (node (ref "C4") (pin "1") (pintype "passive"))
      (node (ref "C5") (pin "1") (pintype "passive"))
      (node (ref "C6") (pin "1") (pintype "passive"))
      (node (ref "C7") (pin "1") (pintype "passive"))
      (node (ref "C8") (pin "1") (pintype "passive"))
      (node (ref "C9") (pin "1") (pintype "passive"))
      (node (ref "P1") (pin "5") (pinfunction "GND_5") (pintype "passive"))
      (node (ref "P1") (pin "6") (pinfunction "PAD_6") (pintype "passive"))
      (node (ref "P2") (pin "2") (pinfunction "2_2") (pintype "passive"))
      (node (ref "R17") (pin "1") (pintype "passive"))
      (node (ref "R2") (pin "2") (pintype "passive"))
      (node (ref "R20") (pin "1") (pintype "passive"))
      (node (ref "R8") (pin "1") (pintype "passive"))
      (node (ref "R9") (pin "1") (pintype "passive"))
      (node (ref "RP1") (pin "1") (pinfunction "3_1") (pintype "passive"))
      (node (ref "SW2") (pin "2") (pintype "passive"))
      (node (ref "SW3") (pin "2") (pintype "passive"))
      (node (ref "SW4") (pin "2") (pintype "passive"))
      (node (ref "U1") (pin "2") (pinfunction "GND_2") (pintype "passive"))
      (node (ref "U2") (pin "12") (pinfunction "VSSA_12") (pintype "passive"))
      (node (ref "U2") (pin "18") (pinfunction "VSS_18") (pintype "passive"))
      (node (ref "U2") (pin "63") (pinfunction "VSS_63") (pintype "passive"))
      (node (ref "U3") (pin "2") (pinfunction "VSS_2") (pintype "passive"))
      (node (ref "U8") (pin "11") (pinfunction "GND_11") (pintype "passive"))
      (node (ref "U8") (pin "15") (pinfunction "GND_15") (pintype "passive"))
      (node (ref "U8") (pin "17") (pinfunction "PAD_17") (pintype "passive"))
      (node (ref "U8") (pin "3") (pinfunction "GND_3") (pintype "passive"))
      (node (ref "U9") (pin "4") (pinfunction "GND_4") (pintype "passive"))
      (node (ref "X1") (pin "2") (pintype "passive"))
      (node (ref "X1") (pin "4") (pintype "passive"))
    )
    (net (code "43") (name "Net-(D3-Pad1)") (class "Default")
      (node (ref "D3") (pin "1") (pintype "passive"))
      (node (ref "P3") (pin "1") (pinfunction "1_1") (pintype "passive"))
      (node (ref "R6") (pin "2") (pintype "passive"))
    )
    (net (code "44") (name "Net-(D6-Pad1)") (class "Default")
      (node (ref "D6") (pin "1") (pintype "passive"))
      (node (ref "P4") (pin "1") (pinfunction "1_1") (pintype "passive"))
      (node (ref "R7") (pin "2") (pintype "passive"))
    )
    (net (code "45") (name "Net-(D7-Pad1)") (class "Default")
      (node (ref "D7") (pin "1") (pintype "passive"))
      (node (ref "P5") (pin "1") (pinfunction "1_1") (pintype "passive"))
      (node (ref "R32") (pin "2") (pintype "passive"))
    )
    (net (code "46") (name "Net-(D8-Pad1)") (class "Default")
      (node (ref "D8") (pin "1") (pintype "passive"))
      (node (ref "P6") (pin "1") (pinfunction "1_1") (pintype "passive"))
      (node (ref "R33") (pin "2") (pintype "passive"))
    )
    (net (code "47") (name "Net-(D9-Pad1)") (class "Default")
      (node (ref "D9") (pin "1") (pintype "passive"))
      (node (ref "P7") (pin "1") (pinfunction "1_1") (pintype "passive"))
      (node (ref "R34") (pin "2") (pintype "passive"))
    )
    (net (code "48") (name "Net-(D10-Pad1)") (class "Default")
      (node (ref "D10") (pin "1") (pintype "passive"))
      (node (ref "P8") (pin "1") (pinfunction "1_1") (pintype "passive"))
      (node (ref "R35") (pin "2") (pintype "passive"))
    )
    (net (code "49") (name "Net-(D11-Pad1)") (class "Default")
      (node (ref "D11") (pin "1") (pintype "passive"))
      (node (ref "P9") (pin "1") (pinfunction "1_1") (pintype "passive"))
      (node (ref "R36") (pin "2") (pintype "passive"))
    )
    (net (code "50") (name "Net-(D12-Pad1)") (class "Default")
      (node (ref "D12") (pin "1") (pintype "passive"))
      (node (ref "P10") (pin "1") (pinfunction "1_1") (pintype "passive"))
      (node (ref "R37") (pin "2") (pintype "passive"))
    )
    (net (code "51") (name "Net-(D13-Pad1)") (class "Default")
      (node (ref "D13") (pin "1") (pintype "passive"))
      (node (ref "P11") (pin "1") (pinfunction "1_1") (pintype "passive"))
      (node (ref "R38") (pin "2") (pintype "passive"))
    )
    (net (code "52") (name "Net-(D14-Pad1)") (class "Default")
      (node (ref "D14") (pin "1") (pintype "passive"))
      (node (ref "P12") (pin "1") (pinfunction "1_1") (pintype "passive"))
      (node (ref "R39") (pin "2") (pintype "passive"))
    )
    (net (code "53") (name "Net-(D15-Pad1)") (class "Default")
      (node (ref "D15") (pin "1") (pintype "passive"))
      (node (ref "P13") (pin "1") (pinfunction "1_1") (pintype "passive"))
      (node (ref "R40") (pin "2") (pintype "passive"))
    )
    (net (code "54") (name "Net-(D16-Pad1)") (class "Default")
      (node (ref "D16") (pin "1") (pintype "passive"))
      (node (ref "P14") (pin "1") (pinfunction "1_1") (pintype "passive"))
      (node (ref "R41") (pin "2") (pintype "passive"))
    )
    (net (code "55") (name "Net-(D17-Pad1)") (class "Default")
      (node (ref "D17") (pin "1") (pintype "passive"))
      (node (ref "P15") (pin "1") (pinfunction "1_1") (pintype "passive"))
      (node (ref "R42") (pin "2") (pintype "passive"))
    )
    (net (code "56") (name "Net-(D18-Pad1)") (class "Default")
      (node (ref "D18") (pin "1") (pintype "passive"))
      (node (ref "P16") (pin "1") (pinfunction "1_1") (pintype "passive"))
      (node (ref "R43") (pin "2") (pintype "passive"))
    )
    (net (code "57") (name "Net-(D19-Pad1)") (class "Default")
      (node (ref "D19") (pin "1") (pintype "passive"))
      (node (ref "P17") (pin "1") (pinfunction "1_1") (pintype "passive"))
      (node (ref "R44") (pin "2") (pintype "passive"))
    )
    (net (code "58") (name "Net-(D20-Pad1)") (class "Default")
      (node (ref "D20") (pin "1") (pintype "passive"))
      (node (ref "P18") (pin "1") (pinfunction "1_1") (pintype "passive"))
      (node (ref "R45") (pin "2") (pintype "passive"))
    )
    (net (code "59") (name "Net-(D21-Pad1)") (class "Default")
      (node (ref "D21") (pin "1") (pintype "passive"))
      (node (ref "P19") (pin "1") (pinfunction "1_1") (pintype "passive"))
      (node (ref "R46") (pin "2") (pintype "passive"))
    )
    (net (code "60") (name "Net-(D22-Pad1)") (class "Default")
      (node (ref "D22") (pin "1") (pintype "passive"))
      (node (ref "P20") (pin "1") (pinfunction "1_1") (pintype "passive"))
      (node (ref "R47") (pin "2") (pintype "passive"))
    )
    (net (code "61") (name "Net-(D23-Pad1)") (class "Default")
      (node (ref "D23") (pin "1") (pintype "passive"))
      (node (ref "P21") (pin "1") (pinfunction "1_1") (pintype "passive"))
      (node (ref "R48") (pin "2") (pintype "passive"))
    )
    (net (code "62") (name "Net-(D24-Pad1)") (class "Default")
      (node (ref "D24") (pin "1") (pintype "passive"))
      (node (ref "P22") (pin "1") (pinfunction "1_1") (pintype "passive"))
      (node (ref "R49") (pin "2") (pintype "passive"))
    )
    (net (code "63") (name "Net-(D25-Pad1)") (class "Default")
      (node (ref "D25") (pin "1") (pintype "passive"))
      (node (ref "P23") (pin "1") (pinfunction "1_1") (pintype "passive"))
      (node (ref "R50") (pin "2") (pintype "passive"))
    )
    (net (code "64") (name "Net-(D26-Pad1)") (class "Default")
      (node (ref "D26") (pin "1") (pintype "passive"))
      (node (ref "P24") (pin "1") (pinfunction "1_1") (pintype "passive"))
      (node (ref "R51") (pin "2") (pintype "passive"))
    )
    (net (code "65") (name "Net-(D27-Pad1)") (class "Default")
      (node (ref "D27") (pin "1") (pintype "passive"))
      (node (ref "P25") (pin "1") (pinfunction "1_1") (pintype "passive"))
      (node (ref "R52") (pin "2") (pintype "passive"))
    )
    (net (code "66") (name "Net-(D28-Pad1)") (class "Default")
      (node (ref "D28") (pin "1") (pintype "passive"))
      (node (ref "P26") (pin "1") (pinfunction "1_1") (pintype "passive"))
      (node (ref "R53") (pin "2") (pintype "passive"))
    )
    (net (code "67") (name "Net-(D29-Pad1)") (class "Default")
      (node (ref "D29") (pin "1") (pintype "passive"))
      (node (ref "P27") (pin "1") (pinfunction "1_1") (pintype "passive"))
      (node (ref "R54") (pin "2") (pintype "passive"))
    )
    (net (code "68") (name "Net-(D30-Pad1)") (class "Default")
      (node (ref "D30") (pin "1") (pintype "passive"))
      (node (ref "P28") (pin "1") (pinfunction "1_1") (pintype "passive"))
      (node (ref "R55") (pin "2") (pintype "passive"))
    )
    (net (code "69") (name "Net-(D31-Pad1)") (class "Default")
      (node (ref "D31") (pin "1") (pintype "passive"))
      (node (ref "P29") (pin "1") (pinfunction "1_1") (pintype "passive"))
      (node (ref "R56") (pin "2") (pintype "passive"))
    )
    (net (code "70") (name "Net-(D32-Pad1)") (class "Default")
      (node (ref "D32") (pin "1") (pintype "passive"))
      (node (ref "P30") (pin "1") (pinfunction "1_1") (pintype "passive"))
      (node (ref "R57") (pin "2") (pintype "passive"))
    )
    (net (code "71") (name "Net-(D33-Pad1)") (class "Default")
      (node (ref "D33") (pin "1") (pintype "passive"))
      (node (ref "P31") (pin "1") (pinfunction "1_1") (pintype "passive"))
      (node (ref "R58") (pin "2") (pintype "passive"))
    )
    (net (code "72") (name "Net-(D34-Pad1)") (class "Default")
      (node (ref "D34") (pin "1") (pintype "passive"))
      (node (ref "P32") (pin "1") (pinfunction "1_1") (pintype "passive"))
      (node (ref "R59") (pin "2") (pintype "passive"))
    )
    (net (code "73") (name "Net-(D35-Pad1)") (class "Default")
      (node (ref "D35") (pin "1") (pintype "passive"))
      (node (ref "P33") (pin "1") (pinfunction "1_1") (pintype "passive"))
      (node (ref "R60") (pin "2") (pintype "passive"))
    )
    (net (code "74") (name "Net-(D36-Pad1)") (class "Default")
      (node (ref "D36") (pin "1") (pintype "passive"))
      (node (ref "P34") (pin "1") (pinfunction "1_1") (pintype "passive"))
      (node (ref "R61") (pin "2") (pintype "passive"))
    )
    (net (code "75") (name "Net-(D37-Pad1)") (class "Default")
      (node (ref "D37") (pin "1") (pintype "passive"))
      (node (ref "P35") (pin "1") (pinfunction "1_1") (pintype "passive"))
      (node (ref "R62") (pin "2") (pintype "passive"))
    )
    (net (code "76") (name "Net-(D38-Pad1)") (class "Default")
      (node (ref "D38") (pin "1") (pintype "passive"))
      (node (ref "P36") (pin "1") (pinfunction "1_1") (pintype "passive"))
      (node (ref "R63") (pin "2") (pintype "passive"))
    )
    (net (code "77") (name "Net-(D39-Pad1)") (class "Default")
      (node (ref "D39") (pin "1") (pintype "passive"))
      (node (ref "P37") (pin "1") (pinfunction "1_1") (pintype "passive"))
      (node (ref "R64") (pin "2") (pintype "passive"))
    )
    (net (code "78") (name "Net-(D40-Pad1)") (class "Default")
      (node (ref "D40") (pin "1") (pintype "passive"))
      (node (ref "P38") (pin "1") (pinfunction "1_1") (pintype "passive"))
      (node (ref "R65") (pin "2") (pintype "passive"))
    )
    (net (code "79") (name "Net-(D41-Pad1)") (class "Default")
      (node (ref "D41") (pin "1") (pintype "passive"))
      (node (ref "P39") (pin "1") (pinfunction "1_1") (pintype "passive"))
      (node (ref "R66") (pin "2") (pintype "passive"))
    )
    (net (code "80") (name "Net-(D42-Pad1)") (class "Default")
      (node (ref "D42") (pin "1") (pintype "passive"))
      (node (ref "P40") (pin "1") (pinfunction "1_1") (pintype "passive"))
      (node (ref "R67") (pin "2") (pintype "passive"))
    )
    (net (code "81") (name "Net-(D43-Pad1)") (class "Default")
      (node (ref "D43") (pin "1") (pintype "passive"))
      (node (ref "P41") (pin "1") (pinfunction "1_1") (pintype "passive"))
      (node (ref "R68") (pin "2") (pintype "passive"))
    )
    (net (code "82") (name "Net-(D44-Pad1)") (class "Default")
      (node (ref "D44") (pin "1") (pintype "passive"))
      (node (ref "P42") (pin "1") (pinfunction "1_1") (pintype "passive"))
      (node (ref "R69") (pin "2") (pintype "passive"))
    )
    (net (code "83") (name "Net-(D45-Pad1)") (class "Default")
      (node (ref "D45") (pin "1") (pintype "passive"))
      (node (ref "P43") (pin "1") (pinfunction "1_1") (pintype "passive"))
      (node (ref "R70") (pin "2") (pintype "passive"))
    )
    (net (code "84") (name "Net-(D46-Pad1)") (class "Default")
      (node (ref "D46") (pin "1") (pintype "passive"))
      (node (ref "P44") (pin "1") (pinfunction "1_1") (pintype "passive"))
      (node (ref "R71") (pin "2") (pintype "passive"))
    )
    (net (code "85") (name "Net-(LED1-Pad1)") (class "Default")
      (node (ref "LED1") (pin "1") (pintype "passive"))
      (node (ref "R1") (pin "1") (pintype "passive"))
    )
    (net (code "86") (name "Net-(LED1-Pad2)") (class "Default")
      (node (ref "LED1") (pin "2") (pintype "passive"))
      (node (ref "R3") (pin "1") (pintype "passive"))
    )
    (net (code "87") (name "Net-(LED2-Pad1)") (class "Default")
      (node (ref "LED2") (pin "1") (pintype "passive"))
      (node (ref "R19") (pin "1") (pintype "passive"))
    )
    (net (code "88") (name "Net-(LED2-Pad2)") (class "Default")
      (node (ref "LED2") (pin "2") (pintype "passive"))
      (node (ref "R21") (pin "1") (pintype "passive"))
    )
    (net (code "89") (name "Net-(LED2-Pad3)") (class "Default")
      (node (ref "LED2") (pin "3") (pintype "passive"))
      (node (ref "R22") (pin "1") (pintype "passive"))
    )
    (net (code "90") (name "Net-(U1-CHRG)") (class "Default")
      (node (ref "R1") (pin "2") (pintype "passive"))
      (node (ref "U1") (pin "1") (pinfunction "CHRG_1") (pintype "passive"))
    )
    (net (code "91") (name "Net-(U1-PROG)") (class "Default")
      (node (ref "R2") (pin "1") (pintype "passive"))
      (node (ref "U1") (pin "6") (pinfunction "PROG_6") (pintype "passive"))
    )
    (net (code "92") (name "Net-(U1-STBY)") (class "Default")
      (node (ref "R3") (pin "2") (pintype "passive"))
      (node (ref "U1") (pin "5") (pinfunction "STBY_5") (pintype "passive"))
    )
    (net (code "93") (name "Net-(U2A-BOOT0)") (class "Default")
      (node (ref "R9") (pin "2") (pintype "passive"))
      (node (ref "U2") (pin "60") (pinfunction "BOOT0_60") (pintype "passive"))
    )
    (net (code "94") (name "Net-(U2A-PB2{slash}BOOT1)") (class "Default")
      (node (ref "R8") (pin "2") (pintype "passive"))
      (node (ref "U2") (pin "28") (pinfunction "PB2/BOOT1_28") (pintype "passive"))
    )
    (net (code "95") (name "Net-(U8-GAIN_SLOT)") (class "Default")
      (node (ref "R16") (pin "2") (pintype "passive"))
      (node (ref "R17") (pin "2") (pintype "passive"))
      (node (ref "U8") (pin "2") (pinfunction "GAIN_SLOT_2") (pintype "passive"))
    )
    (net (code "96") (name "VBAT") (class "Default")
      (node (ref "P2") (pin "1") (pinfunction "1_1") (pintype "passive"))
      (node (ref "SW1") (pin "2") (pintype "passive"))
      (node (ref "U1") (pin "3") (pinfunction "BAT_3") (pintype "passive"))
    )
    (net (code "97") (name "VBUS") (class "Default")
      (node (ref "C1") (pin "2") (pintype "passive"))
      (node (ref "LED1") (pin "4") (pintype "passive"))
      (node (ref "P1") (pin "1") (pinfunction "VCC_1") (pintype "passive"))
      (node (ref "U1") (pin "4") (pinfunction "VCC_4") (pintype "passive"))
    )
    (net (code "98") (name "VCC") (class "Default")
      (node (ref "C10") (pin "2") (pintype "passive"))
      (node (ref "C12") (pin "2") (pintype "passive"))
      (node (ref "C4") (pin "2") (pintype "passive"))
      (node (ref "C5") (pin "2") (pintype "passive"))
      (node (ref "C7") (pin "2") (pintype "passive"))
      (node (ref "C8") (pin "2") (pintype "passive"))
      (node (ref "C9") (pin "2") (pintype "passive"))
      (node (ref "LED2") (pin "4") (pintype "passive"))
      (node (ref "R23") (pin "1") (pintype "passive"))
      (node (ref "R24") (pin "1") (pintype "passive"))
      (node (ref "R5") (pin "1") (pintype "passive"))
      (node (ref "RP1") (pin "4") (pintype "passive"))
      (node (ref "U2") (pin "1") (pinfunction "VBAT_1") (pintype "passive"))
      (node (ref "U2") (pin "13") (pinfunction "VDDA_13") (pintype "passive"))
      (node (ref "U2") (pin "19") (pinfunction "VDD_19") (pintype "passive"))
      (node (ref "U2") (pin "32") (pinfunction "VDD_32") (pintype "passive"))
      (node (ref "U2") (pin "48") (pinfunction "VDD_48") (pintype "passive"))
      (node (ref "U2") (pin "64") (pinfunction "VDD_64") (pintype "passive"))
      (node (ref "U3") (pin "5") (pinfunction "VOUT_5") (pintype "passive"))
    )
    (net (code "99") (name "VCC_MCU") (class "Default")
      (node (ref "C24") (pin "2") (pintype "passive"))
      (node (ref "U9") (pin "8") (pinfunction "VCC_8") (pintype "passive"))
    )
    (net (code "100") (name "unconnected-(LED1-Pad3)") (class "Default")
      (node (ref "LED1") (pin "3") (pintype "passive"))
    )
    (net (code "101") (name "unconnected-(P1-ID-Pad4)") (class "Default")
      (node (ref "P1") (pin "4") (pinfunction "ID_4") (pintype "passive"))
    )
    (net (code "102") (name "unconnected-(RP1-Pad2)") (class "Default")
      (node (ref "RP1") (pin "2") (pintype "passive"))
    )
    (net (code "103") (name "unconnected-(RP1-Pad5)") (class "Default")
      (node (ref "RP1") (pin "5") (pintype "passive"))
    )
    (net (code "104") (name "unconnected-(SW1-Pad3)") (class "Default")
      (node (ref "SW1") (pin "3") (pintype "passive"))
    )
    (net (code "105") (name "unconnected-(U2A-PA1-Pad15)") (class "Default")
      (node (ref "U2") (pin "15") (pinfunction "PA1_15") (pintype "passive"))
    )
    (net (code "106") (name "unconnected-(U2A-PA2-Pad16)") (class "Default")
      (node (ref "U2") (pin "16") (pinfunction "PA2_16") (pintype "passive"))
    )
    (net (code "107") (name "unconnected-(U2A-PA4-Pad20)") (class "Default")
      (node (ref "U2") (pin "20") (pinfunction "PA4_20") (pintype "passive"))
    )
    (net (code "108") (name "unconnected-(U2A-PA5-Pad21)") (class "Default")
      (node (ref "U2") (pin "21") (pinfunction "PA5_21") (pintype "passive"))
    )
    (net (code "109") (name "unconnected-(U2A-PA12-Pad45)") (class "Default")
      (node (ref "U2") (pin "45") (pinfunction "PA12_45") (pintype "passive"))
    )
    (net (code "110") (name "unconnected-(U2A-PA15-Pad50)") (class "Default")
      (node (ref "U2") (pin "50") (pinfunction "PA15_50") (pintype "passive"))
    )
    (net (code "111") (name "unconnected-(U2A-PB0-Pad26)") (class "Default")
      (node (ref "U2") (pin "26") (pinfunction "PB0_26") (pintype "passive"))
    )
    (net (code "112") (name "unconnected-(U2A-PB3-Pad55)") (class "Default")
      (node (ref "U2") (pin "55") (pinfunction "PB3_55") (pintype "passive"))
    )
    (net (code "113") (name "unconnected-(U2A-PB4-Pad56)") (class "Default")
      (node (ref "U2") (pin "56") (pinfunction "PB4_56") (pintype "passive"))
    )
    (net (code "114") (name "unconnected-(U2A-PB5-Pad57)") (class "Default")
      (node (ref "U2") (pin "57") (pinfunction "PB5_57") (pintype "passive"))
    )
    (net (code "115") (name "unconnected-(U2A-PB11-Pad30)") (class "Default")
      (node (ref "U2") (pin "30") (pinfunction "PB11_30") (pintype "passive"))
    )
    (net (code "116") (name "unconnected-(U2A-PC10-Pad51)") (class "Default")
      (node (ref "U2") (pin "51") (pinfunction "PC10_51") (pintype "passive"))
    )
    (net (code "117") (name "unconnected-(U2A-PC11-Pad52)") (class "Default")
      (node (ref "U2") (pin "52") (pinfunction "PC11_52") (pintype "passive"))
    )
    (net (code "118") (name "unconnected-(U2A-PC12-Pad53)") (class "Default")
      (node (ref "U2") (pin "53") (pinfunction "PC12_53") (pintype "passive"))
    )
    (net (code "119") (name "unconnected-(U2A-PD2-Pad54)") (class "Default")
      (node (ref "U2") (pin "54") (pinfunction "PD2_54") (pintype "passive"))
    )
    (net (code "120") (name "unconnected-(U2A-PH2-Pad47)") (class "Default")
      (node (ref "U2") (pin "47") (pinfunction "PH2_47") (pintype "passive"))
    )
    (net (code "121") (name "unconnected-(U2A-PH3-Pad31)") (class "Default")
      (node (ref "U2") (pin "31") (pinfunction "PH3_31") (pintype "passive"))
    )
    (net (code "122") (name "unconnected-(U3-NC-Pad4)") (class "Default")
      (node (ref "U3") (pin "4") (pinfunction "NC_4") (pintype "passive"))
    )
    (net (code "123") (name "unconnected-(U8-NC-Pad5)") (class "Default")
      (node (ref "U8") (pin "5") (pinfunction "NC_5") (pintype "passive"))
    )
    (net (code "124") (name "unconnected-(U8-NC-Pad6)") (class "Default")
      (node (ref "U8") (pin "6") (pinfunction "NC_6") (pintype "passive"))
    )
    (net (code "125") (name "unconnected-(U8-NC-Pad12)") (class "Default")
      (node (ref "U8") (pin "12") (pinfunction "NC_12") (pintype "passive"))
    )
    (net (code "126") (name "unconnected-(U8-NC-Pad13)") (class "Default")
      (node (ref "U8") (pin "13") (pinfunction "NC_13") (pintype "passive"))
    )
  )
)
